# ThermostatAVT1742.net
KiCad netlist of a schematic drawn in EAGLE
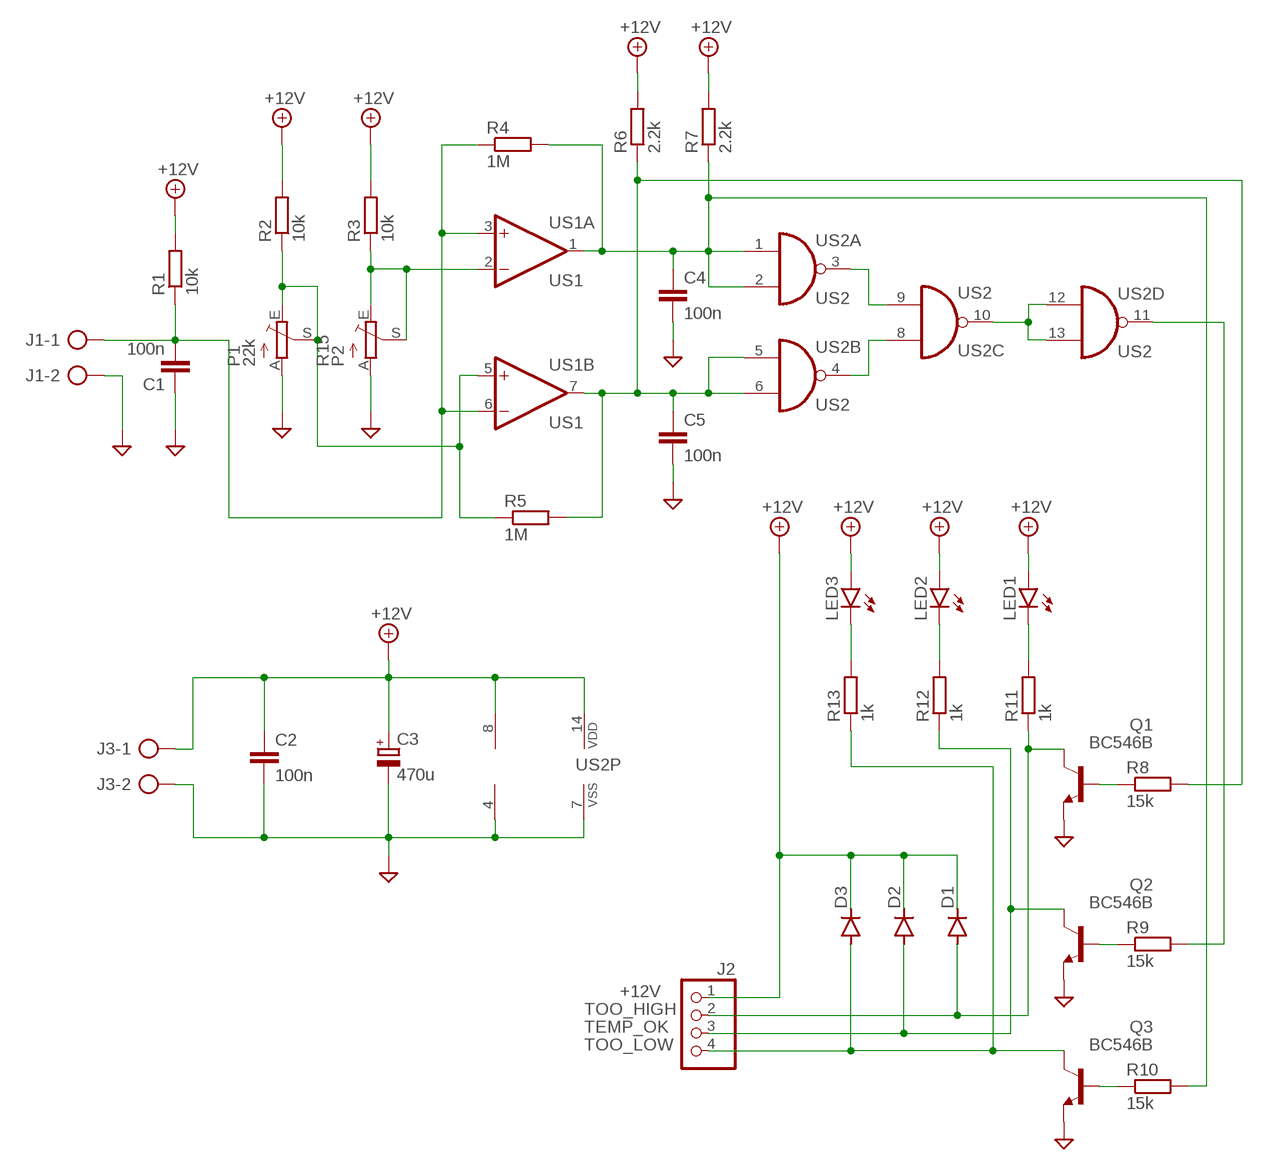
[diagram p0: schematic, sheet 1]

(export (version "E")
  (design (tool "Eeschema 10.0.6"))
  (components
    (comp (ref "C1")
      (value "100n")
      (footprint "eagle-import:C050-025X075")
      (libsource (lib "eagle-import") (part "C-EU050-025X075"))
    )
    (comp (ref "C2")
      (value "100n")
      (footprint "eagle-import:C050-025X075")
      (libsource (lib "eagle-import") (part "C-EU050-025X075"))
    )
    (comp (ref "C3")
      (value "470u")
      (footprint "eagle-import:E3,5-8")
      (libsource (lib "eagle-import") (part "CPOL-EUE3.5-8"))
    )
    (comp (ref "C4")
      (value "100n")
      (footprint "eagle-import:C050-025X075")
      (libsource (lib "eagle-import") (part "C-EU050-025X075"))
    )
    (comp (ref "C5")
      (value "100n")
      (footprint "eagle-import:C050-025X075")
      (libsource (lib "eagle-import") (part "C-EU050-025X075"))
    )
    (comp (ref "D1")
      (value "red")
      (footprint "eagle-import:DO35-10")
      (libsource (lib "eagle-import") (part "1N4148DO35-10"))
    )
    (comp (ref "D2")
      (value "green")
      (footprint "eagle-import:DO35-10")
      (libsource (lib "eagle-import") (part "1N4148DO35-10"))
    )
    (comp (ref "D3")
      (value "yellow")
      (footprint "eagle-import:DO35-10")
      (libsource (lib "eagle-import") (part "1N4148DO35-10"))
    )
    (comp (ref "J1")
      (value "J1")
      (footprint "eagle-import:AK500_2")
      (libsource (lib "eagle-import") (part "AK500/2"))
    )
    (comp (ref "J2")
      (value "J2")
      (footprint "eagle-import:1X04")
      (libsource (lib "eagle-import") (part "PINHD-1X4"))
    )
    (comp (ref "J3")
      (value "J3")
      (footprint "eagle-import:AK500_2")
      (libsource (lib "eagle-import") (part "AK500/2"))
    )
    (comp (ref "LED1")
      (value "red")
      (footprint "eagle-import:LED5MM")
      (libsource (lib "eagle-import") (part "LED5MM"))
    )
    (comp (ref "LED2")
      (value "green")
      (footprint "eagle-import:LED5MM")
      (libsource (lib "eagle-import") (part "LED5MM"))
    )
    (comp (ref "LED3")
      (value "yellow")
      (footprint "eagle-import:LED5MM")
      (libsource (lib "eagle-import") (part "LED5MM"))
    )
    (comp (ref "P1")
      (value "22k")
      (footprint "eagle-import:CA6V")
      (libsource (lib "eagle-import") (part "TRIM_EU-CA6V"))
    )
    (comp (ref "Q1")
      (value "BC546B")
      (footprint "eagle-import:TO92-EBC")
      (libsource (lib "eagle-import") (part "BC546B"))
    )
    (comp (ref "Q2")
      (value "BC546B")
      (footprint "eagle-import:TO92-EBC")
      (libsource (lib "eagle-import") (part "BC546B"))
    )
    (comp (ref "Q3")
      (value "BC546B")
      (footprint "eagle-import:TO92-EBC")
      (libsource (lib "eagle-import") (part "BC546B"))
    )
    (comp (ref "R1")
      (value "10k")
      (footprint "eagle-import:0207_10")
      (libsource (lib "eagle-import") (part "R-EU_0207/10"))
    )
    (comp (ref "R2")
      (value "10k")
      (footprint "eagle-import:0207_10")
      (libsource (lib "eagle-import") (part "R-EU_0207/10"))
    )
    (comp (ref "R3")
      (value "10k")
      (footprint "eagle-import:0207_10")
      (libsource (lib "eagle-import") (part "R-EU_0207/10"))
    )
    (comp (ref "R4")
      (value "1M")
      (footprint "eagle-import:0207_10")
      (libsource (lib "eagle-import") (part "R-EU_0207/10"))
    )
    (comp (ref "R5")
      (value "1M")
      (footprint "eagle-import:0207_10")
      (libsource (lib "eagle-import") (part "R-EU_0207/10"))
    )
    (comp (ref "R6")
      (value "2.2k")
      (footprint "eagle-import:0207_10")
      (libsource (lib "eagle-import") (part "R-EU_0207/10"))
    )
    (comp (ref "R7")
      (value "2.2k")
      (footprint "eagle-import:0207_10")
      (libsource (lib "eagle-import") (part "R-EU_0207/10"))
    )
    (comp (ref "R8")
      (value "15k")
      (footprint "eagle-import:0207_10")
      (libsource (lib "eagle-import") (part "R-EU_0207/10"))
    )
    (comp (ref "R9")
      (value "15k")
      (footprint "eagle-import:0207_10")
      (libsource (lib "eagle-import") (part "R-EU_0207/10"))
    )
    (comp (ref "R10")
      (value "15k")
      (footprint "eagle-import:0207_10")
      (libsource (lib "eagle-import") (part "R-EU_0207/10"))
    )
    (comp (ref "R11")
      (value "1k")
      (footprint "eagle-import:0207_10")
      (libsource (lib "eagle-import") (part "R-EU_0207/10"))
    )
    (comp (ref "R12")
      (value "1k")
      (footprint "eagle-import:0207_10")
      (libsource (lib "eagle-import") (part "R-EU_0207/10"))
    )
    (comp (ref "R13")
      (value "1k")
      (footprint "eagle-import:0207_10")
      (libsource (lib "eagle-import") (part "R-EU_0207/10"))
    )
    (comp (ref "R15")
      (value "P2")
      (footprint "eagle-import:CA6V")
      (libsource (lib "eagle-import") (part "TRIM_EU-CA6V"))
    )
    (comp (ref "US1")
      (value "US1")
      (footprint "eagle-import:DIL08")
      (libsource (lib "eagle-import") (part "LM393N"))
    )
    (comp (ref "US2")
      (value "US2")
      (footprint "eagle-import:DIL14")
      (libsource (lib "eagle-import") (part "4011N"))
    )
  )
  (nets
    (net (code "1") (name "+12V") (class "Default")
      (node (ref "C2") (pin "1") (pinfunction "1_1") (pintype "passive"))
      (node (ref "C3") (pin "+") (pinfunction "+_+") (pintype "passive"))
      (node (ref "D1") (pin "C") (pinfunction "C_C") (pintype "passive"))
      (node (ref "D2") (pin "C") (pinfunction "C_C") (pintype "passive"))
      (node (ref "D3") (pin "C") (pinfunction "C_C") (pintype "passive"))
      (node (ref "J2") (pin "1") (pinfunction "1_1") (pintype "passive"))
      (node (ref "J3") (pin "1") (pinfunction "KL_1") (pintype "passive"))
      (node (ref "LED1") (pin "A") (pinfunction "A_A") (pintype "passive"))
      (node (ref "LED2") (pin "A") (pinfunction "A_A") (pintype "passive"))
      (node (ref "LED3") (pin "A") (pinfunction "A_A") (pintype "passive"))
      (node (ref "R1") (pin "2") (pinfunction "2_2") (pintype "passive"))
      (node (ref "R2") (pin "2") (pinfunction "2_2") (pintype "passive"))
      (node (ref "R3") (pin "2") (pinfunction "2_2") (pintype "passive"))
      (node (ref "R6") (pin "2") (pinfunction "2_2") (pintype "passive"))
      (node (ref "R7") (pin "2") (pinfunction "2_2") (pintype "passive"))
      (node (ref "US1") (pin "8") (pinfunction "V+_8") (pintype "power_in"))
      (node (ref "US2") (pin "14") (pinfunction "VDD_14") (pintype "power_in"))
    )
    (net (code "2") (name "/TEMP_OK") (class "Default")
      (node (ref "D2") (pin "A") (pinfunction "A_A") (pintype "passive"))
      (node (ref "J2") (pin "3") (pinfunction "3_3") (pintype "passive"))
      (node (ref "Q2") (pin "C") (pinfunction "C_C") (pintype "passive"))
      (node (ref "R12") (pin "1") (pinfunction "1_1") (pintype "passive"))
    )
    (net (code "3") (name "/TOO_HIGH") (class "Default")
      (node (ref "D1") (pin "A") (pinfunction "A_A") (pintype "passive"))
      (node (ref "J2") (pin "2") (pinfunction "2_2") (pintype "passive"))
      (node (ref "Q1") (pin "C") (pinfunction "C_C") (pintype "passive"))
      (node (ref "R11") (pin "1") (pinfunction "1_1") (pintype "passive"))
    )
    (net (code "4") (name "/TOO_LOW") (class "Default")
      (node (ref "D3") (pin "A") (pinfunction "A_A") (pintype "passive"))
      (node (ref "J2") (pin "4") (pinfunction "4_4") (pintype "passive"))
      (node (ref "Q3") (pin "C") (pinfunction "C_C") (pintype "passive"))
      (node (ref "R13") (pin "1") (pinfunction "1_1") (pintype "passive"))
    )
    (net (code "5") (name "GND") (class "Default")
      (node (ref "C1") (pin "1") (pinfunction "1_1") (pintype "passive"))
      (node (ref "C2") (pin "2") (pinfunction "2_2") (pintype "passive"))
      (node (ref "C3") (pin "-") (pinfunction "-_-") (pintype "passive"))
      (node (ref "C4") (pin "2") (pinfunction "2_2") (pintype "passive"))
      (node (ref "C5") (pin "2") (pinfunction "2_2") (pintype "passive"))
      (node (ref "J1") (pin "2") (pinfunction "KL_2") (pintype "passive"))
      (node (ref "J3") (pin "2") (pinfunction "KL_2") (pintype "passive"))
      (node (ref "P1") (pin "A") (pinfunction "A_A") (pintype "passive"))
      (node (ref "Q1") (pin "E") (pinfunction "E_E") (pintype "passive"))
      (node (ref "Q2") (pin "E") (pinfunction "E_E") (pintype "passive"))
      (node (ref "Q3") (pin "E") (pinfunction "E_E") (pintype "passive"))
      (node (ref "R15") (pin "A") (pinfunction "A_A") (pintype "passive"))
      (node (ref "US1") (pin "4") (pinfunction "V-_4") (pintype "power_in"))
      (node (ref "US2") (pin "7") (pinfunction "VSS_7") (pintype "power_in"))
    )
    (net (code "6") (name "Net-(J1A-KL)") (class "Default")
      (node (ref "C1") (pin "2") (pinfunction "2_2") (pintype "passive"))
      (node (ref "J1") (pin "1") (pinfunction "KL_1") (pintype "passive"))
      (node (ref "R1") (pin "1") (pinfunction "1_1") (pintype "passive"))
      (node (ref "R4") (pin "1") (pinfunction "1_1") (pintype "passive"))
      (node (ref "US1") (pin "3") (pinfunction "+IN_3") (pintype "input"))
      (node (ref "US1") (pin "6") (pinfunction "-IN_6") (pintype "input"))
    )
    (net (code "7") (name "Net-(LED1-C)") (class "Default")
      (node (ref "LED1") (pin "K") (pinfunction "C_K") (pintype "passive"))
      (node (ref "R11") (pin "2") (pinfunction "2_2") (pintype "passive"))
    )
    (net (code "8") (name "Net-(LED2-C)") (class "Default")
      (node (ref "LED2") (pin "K") (pinfunction "C_K") (pintype "passive"))
      (node (ref "R12") (pin "2") (pinfunction "2_2") (pintype "passive"))
    )
    (net (code "9") (name "Net-(LED3-C)") (class "Default")
      (node (ref "LED3") (pin "K") (pinfunction "C_K") (pintype "passive"))
      (node (ref "R13") (pin "2") (pinfunction "2_2") (pintype "passive"))
    )
    (net (code "10") (name "Net-(Q1-PadB)") (class "Default")
      (node (ref "Q1") (pin "B") (pinfunction "B_B") (pintype "passive"))
      (node (ref "R8") (pin "1") (pinfunction "1_1") (pintype "passive"))
    )
    (net (code "11") (name "Net-(Q2-PadB)") (class "Default")
      (node (ref "Q2") (pin "B") (pinfunction "B_B") (pintype "passive"))
      (node (ref "R9") (pin "1") (pinfunction "1_1") (pintype "passive"))
    )
    (net (code "12") (name "Net-(Q3-PadB)") (class "Default")
      (node (ref "Q3") (pin "B") (pinfunction "B_B") (pintype "passive"))
      (node (ref "R10") (pin "1") (pinfunction "1_1") (pintype "passive"))
    )
    (net (code "13") (name "Net-(US1A--IN)") (class "Default")
      (node (ref "R15") (pin "E") (pinfunction "E_E") (pintype "passive"))
      (node (ref "R15") (pin "S") (pinfunction "S_S") (pintype "passive"))
      (node (ref "R3") (pin "1") (pinfunction "1_1") (pintype "passive"))
      (node (ref "US1") (pin "2") (pinfunction "-IN_2") (pintype "input"))
    )
    (net (code "14") (name "Net-(US1A-OUT)") (class "Default")
      (node (ref "C4") (pin "1") (pinfunction "1_1") (pintype "passive"))
      (node (ref "R10") (pin "2") (pinfunction "2_2") (pintype "passive"))
      (node (ref "R4") (pin "2") (pinfunction "2_2") (pintype "passive"))
      (node (ref "R7") (pin "1") (pinfunction "1_1") (pintype "passive"))
      (node (ref "US1") (pin "1") (pinfunction "OUT_1") (pintype "output"))
      (node (ref "US2") (pin "1") (pinfunction "I0_1") (pintype "input"))
      (node (ref "US2") (pin "2") (pinfunction "I1_2") (pintype "input"))
    )
    (net (code "15") (name "Net-(US1B-+IN)") (class "Default")
      (node (ref "P1") (pin "E") (pinfunction "E_E") (pintype "passive"))
      (node (ref "P1") (pin "S") (pinfunction "S_S") (pintype "passive"))
      (node (ref "R2") (pin "1") (pinfunction "1_1") (pintype "passive"))
      (node (ref "R5") (pin "1") (pinfunction "1_1") (pintype "passive"))
      (node (ref "US1") (pin "5") (pinfunction "+IN_5") (pintype "input"))
    )
    (net (code "16") (name "Net-(US1B-OUT)") (class "Default")
      (node (ref "C5") (pin "1") (pinfunction "1_1") (pintype "passive"))
      (node (ref "R5") (pin "2") (pinfunction "2_2") (pintype "passive"))
      (node (ref "R6") (pin "1") (pinfunction "1_1") (pintype "passive"))
      (node (ref "R8") (pin "2") (pinfunction "2_2") (pintype "passive"))
      (node (ref "US1") (pin "7") (pinfunction "OUT_7") (pintype "output"))
      (node (ref "US2") (pin "5") (pinfunction "I0_5") (pintype "input"))
      (node (ref "US2") (pin "6") (pinfunction "I1_6") (pintype "input"))
    )
    (net (code "17") (name "Net-(US2A-O)") (class "Default")
      (node (ref "US2") (pin "3") (pinfunction "O_3") (pintype "output"))
      (node (ref "US2") (pin "9") (pinfunction "I1_9") (pintype "input"))
    )
    (net (code "18") (name "Net-(US2B-O)") (class "Default")
      (node (ref "US2") (pin "4") (pinfunction "O_4") (pintype "output"))
      (node (ref "US2") (pin "8") (pinfunction "I0_8") (pintype "input"))
    )
    (net (code "19") (name "Net-(US2C-O)") (class "Default")
      (node (ref "US2") (pin "10") (pinfunction "O_10") (pintype "output"))
      (node (ref "US2") (pin "12") (pinfunction "I0_12") (pintype "input"))
      (node (ref "US2") (pin "13") (pinfunction "I1_13") (pintype "input"))
    )
    (net (code "20") (name "Net-(US2D-O)") (class "Default")
      (node (ref "R9") (pin "2") (pinfunction "2_2") (pintype "passive"))
      (node (ref "US2") (pin "11") (pinfunction "O_11") (pintype "output"))
    )
  )
)
